# I2C16RJ45.net
KiCad netlist of a schematic drawn in EAGLE
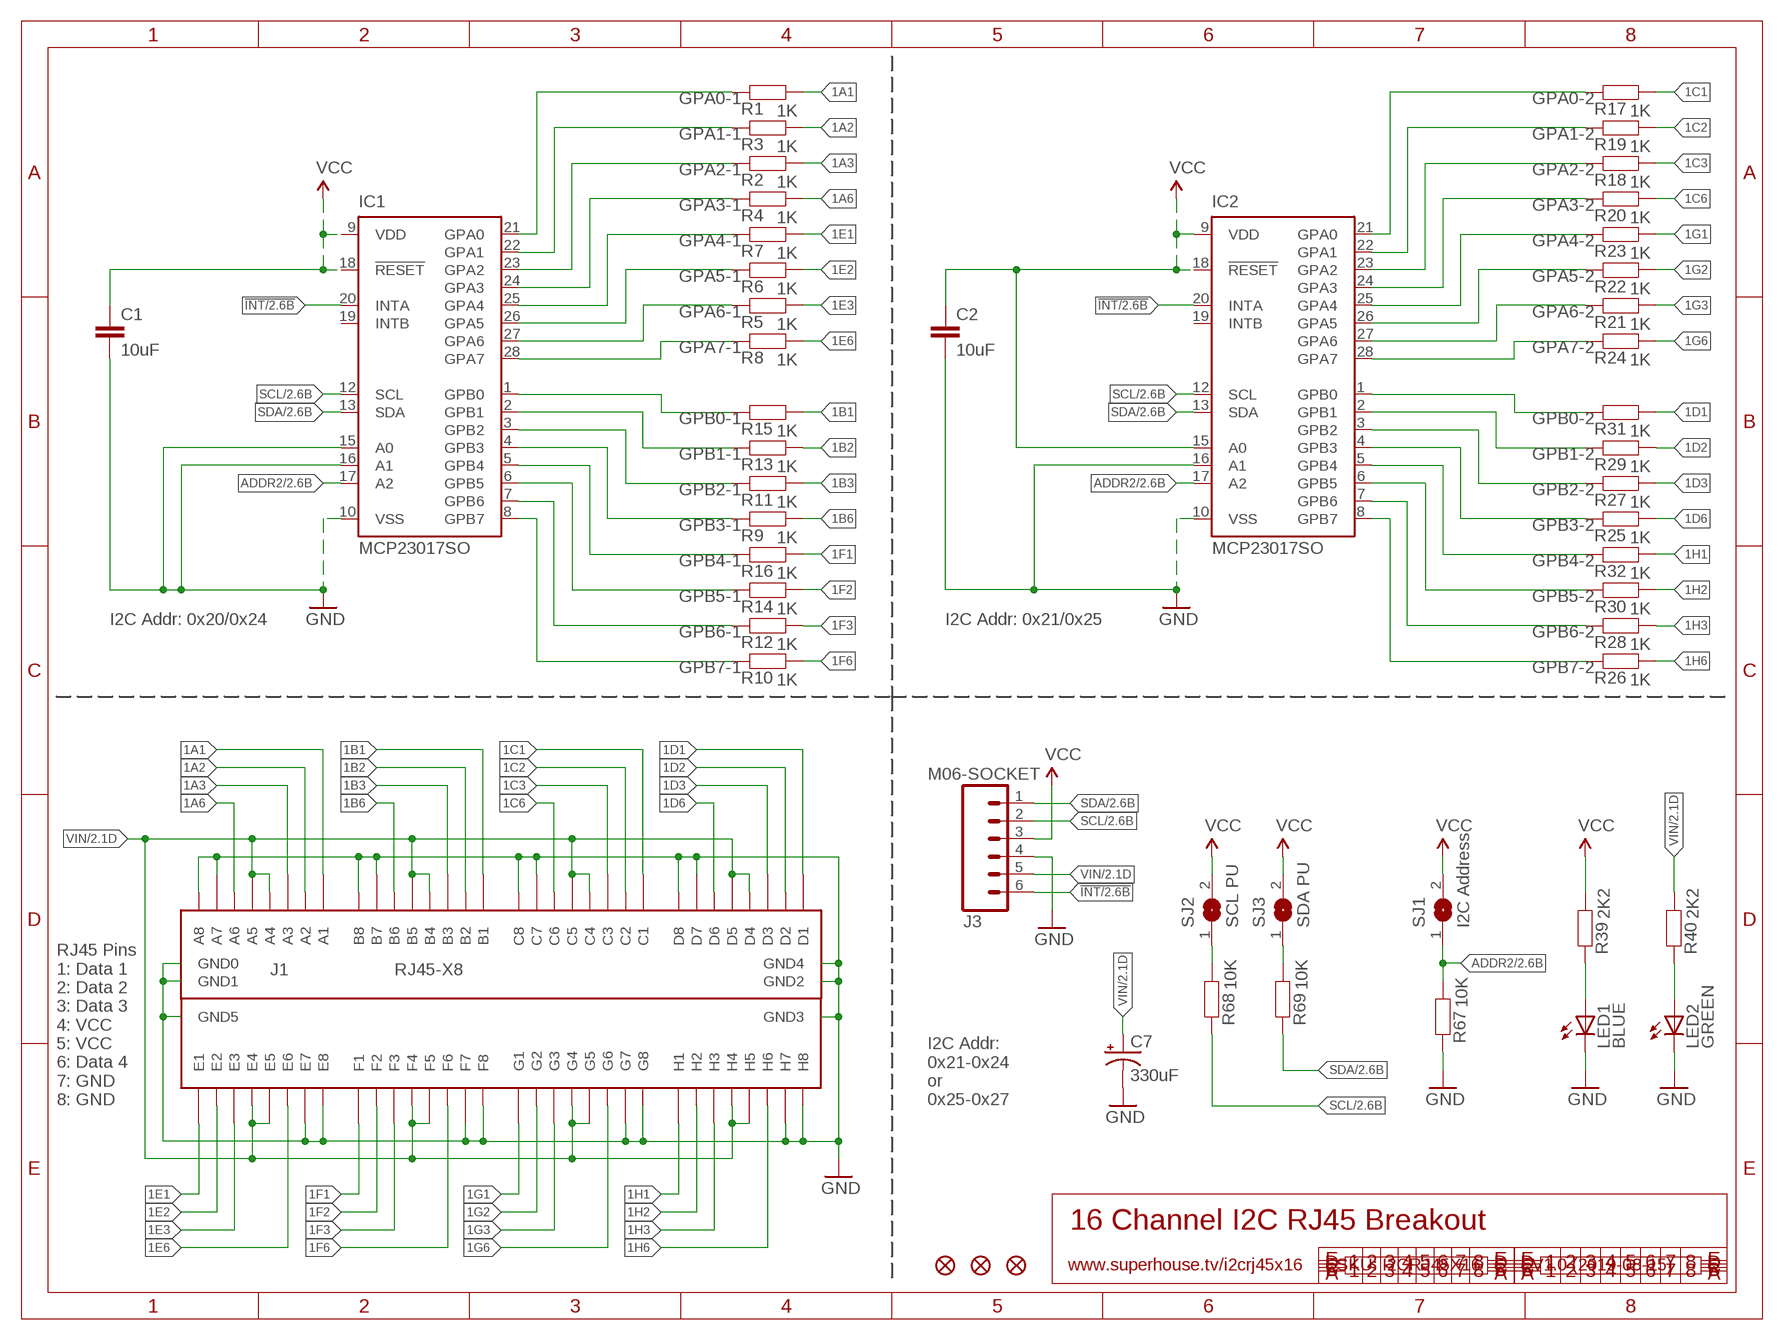
[diagram p0: schematic, sheet 1]
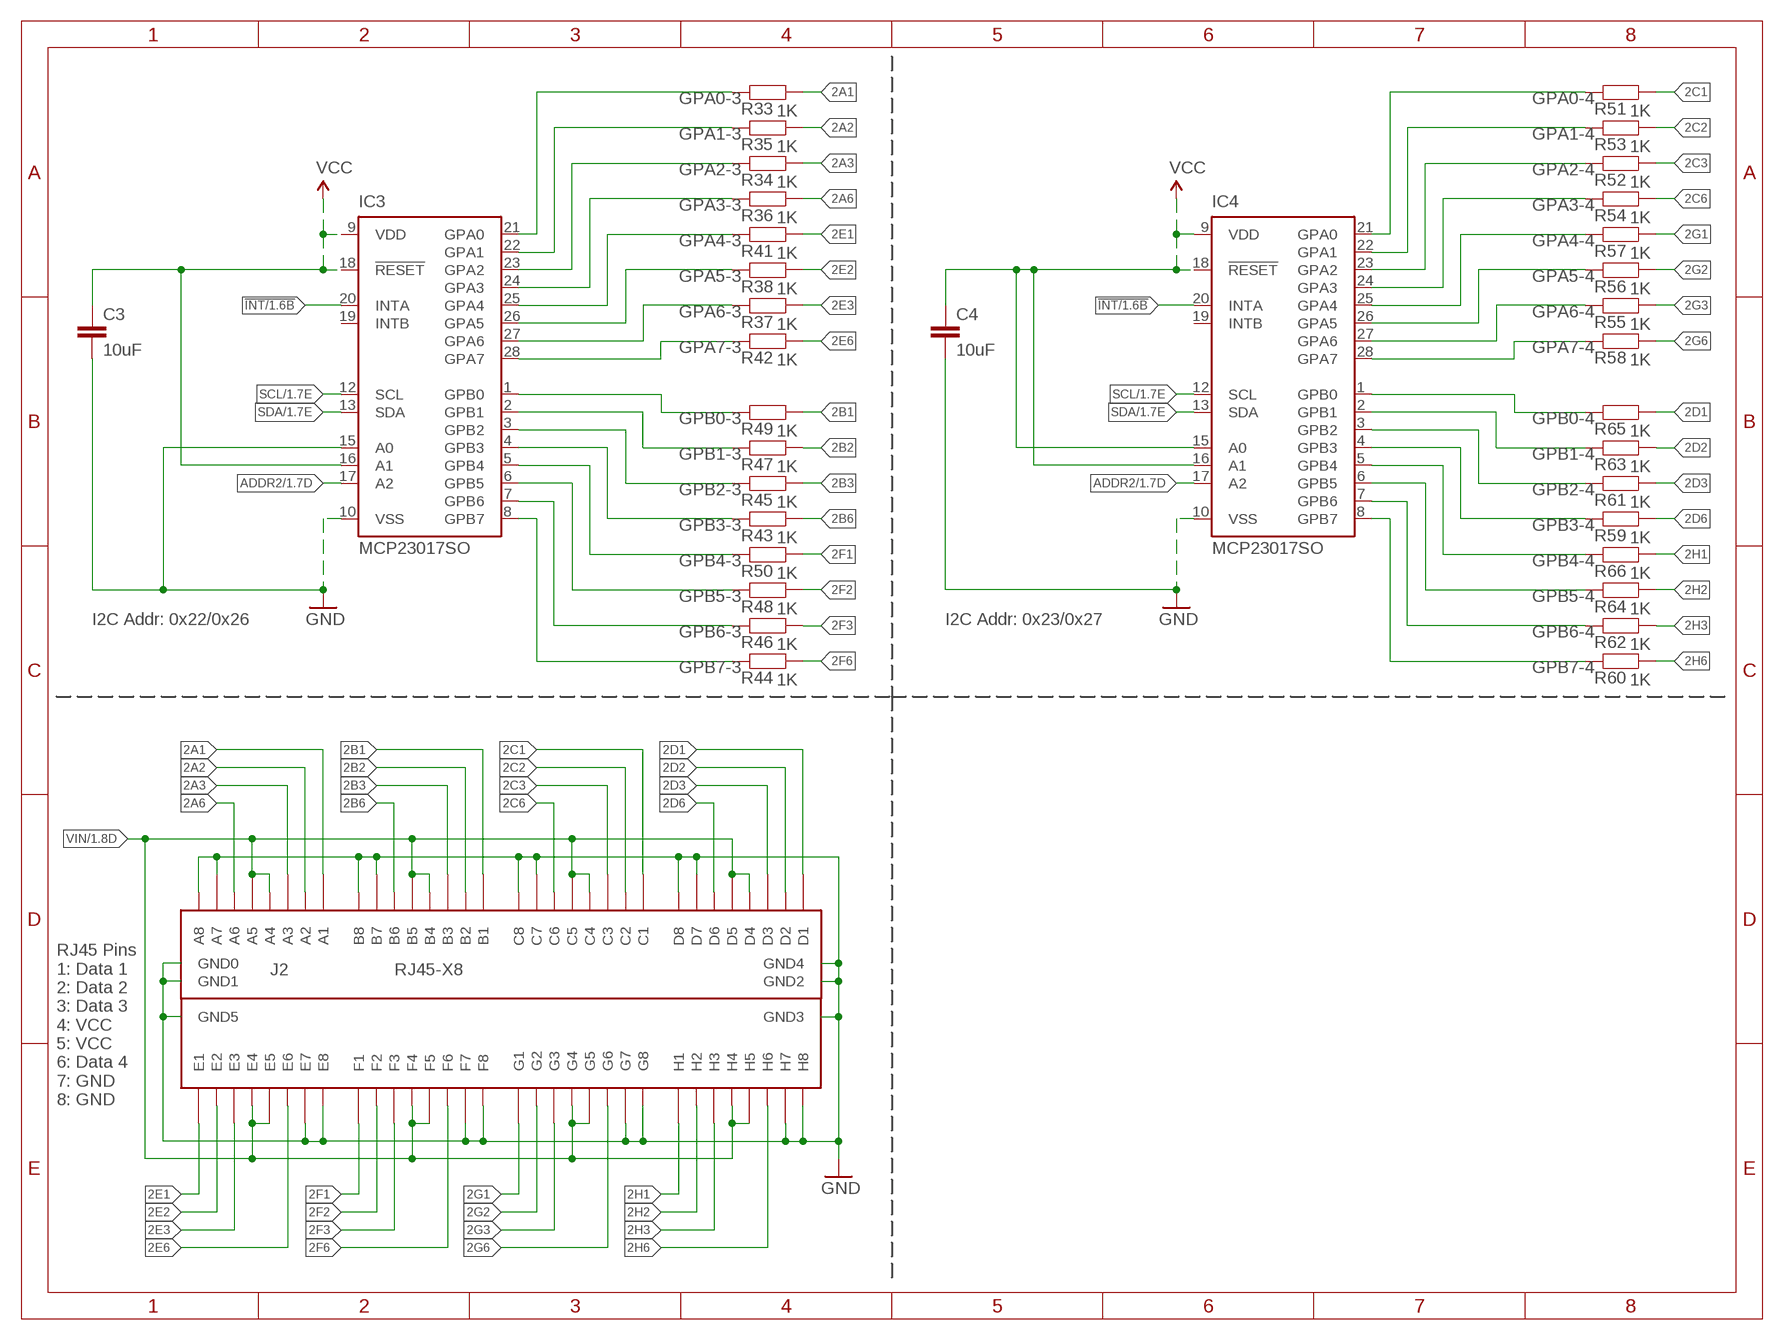
[diagram p1: schematic, sheet 2]

(export (version "E")
  (design (tool "Eeschema 10.0.6"))
  (components
    (comp (ref "C1")
      (value "10uF")
      (footprint "eagle-import:C0805")
      (libsource (lib "eagle-import") (part "CAP0805"))
    )
    (comp (ref "C2")
      (value "10uF")
      (footprint "eagle-import:C0805")
      (libsource (lib "eagle-import") (part "CAP0805"))
    )
    (comp (ref "C7")
      (value "330uF")
      (footprint "eagle-import:PANASONIC_G")
      (libsource (lib "eagle-import") (part "CAP_POLG"))
    )
    (comp (ref "FID1")
      (value "FIDUCIAL1X2.5")
      (footprint "eagle-import:FIDUCIAL-1X2.5")
      (libsource (lib "eagle-import") (part "FIDUCIAL1X2.5"))
    )
    (comp (ref "FID2")
      (value "FIDUCIAL1X2.5")
      (footprint "eagle-import:FIDUCIAL-1X2.5")
      (libsource (lib "eagle-import") (part "FIDUCIAL1X2.5"))
    )
    (comp (ref "FID3")
      (value "FIDUCIAL1X2.5")
      (footprint "eagle-import:FIDUCIAL-1X2.5")
      (libsource (lib "eagle-import") (part "FIDUCIAL1X2.5"))
    )
    (comp (ref "IC1")
      (value "MCP23017SO")
      (footprint "eagle-import:SO28W")
      (libsource (lib "eagle-import") (part "MCP23017SO"))
    )
    (comp (ref "IC2")
      (value "MCP23017SO")
      (footprint "eagle-import:SO28W")
      (libsource (lib "eagle-import") (part "MCP23017SO"))
    )
    (comp (ref "J1")
      (value "RJ45-X8")
      (footprint "eagle-import:RJ45-2X4")
      (libsource (lib "eagle-import") (part "RJ45-X8"))
    )
    (comp (ref "J3")
      (value "M06-SOCKET")
      (footprint "eagle-import:1X06-S")
      (libsource (lib "eagle-import") (part "M06-SOCKET"))
    )
    (comp (ref "LED1")
      (value "BLUE")
      (footprint "eagle-import:LED-0603")
      (libsource (lib "eagle-import") (part "LED0603"))
    )
    (comp (ref "LED2")
      (value "GREEN")
      (footprint "eagle-import:LED-0603")
      (libsource (lib "eagle-import") (part "LED0603"))
    )
    (comp (ref "R1")
      (value "1K")
      (footprint "eagle-import:R0603")
      (libsource (lib "eagle-import") (part "RESISTOR0603"))
    )
    (comp (ref "R2")
      (value "1K")
      (footprint "eagle-import:R0603")
      (libsource (lib "eagle-import") (part "RESISTOR0603"))
    )
    (comp (ref "R3")
      (value "1K")
      (footprint "eagle-import:R0603")
      (libsource (lib "eagle-import") (part "RESISTOR0603"))
    )
    (comp (ref "R4")
      (value "1K")
      (footprint "eagle-import:R0603")
      (libsource (lib "eagle-import") (part "RESISTOR0603"))
    )
    (comp (ref "R5")
      (value "1K")
      (footprint "eagle-import:R0603")
      (libsource (lib "eagle-import") (part "RESISTOR0603"))
    )
    (comp (ref "R6")
      (value "1K")
      (footprint "eagle-import:R0603")
      (libsource (lib "eagle-import") (part "RESISTOR0603"))
    )
    (comp (ref "R7")
      (value "1K")
      (footprint "eagle-import:R0603")
      (libsource (lib "eagle-import") (part "RESISTOR0603"))
    )
    (comp (ref "R8")
      (value "1K")
      (footprint "eagle-import:R0603")
      (libsource (lib "eagle-import") (part "RESISTOR0603"))
    )
    (comp (ref "R9")
      (value "1K")
      (footprint "eagle-import:R0603")
      (libsource (lib "eagle-import") (part "RESISTOR0603"))
    )
    (comp (ref "R10")
      (value "1K")
      (footprint "eagle-import:R0603")
      (libsource (lib "eagle-import") (part "RESISTOR0603"))
    )
    (comp (ref "R11")
      (value "1K")
      (footprint "eagle-import:R0603")
      (libsource (lib "eagle-import") (part "RESISTOR0603"))
    )
    (comp (ref "R12")
      (value "1K")
      (footprint "eagle-import:R0603")
      (libsource (lib "eagle-import") (part "RESISTOR0603"))
    )
    (comp (ref "R13")
      (value "1K")
      (footprint "eagle-import:R0603")
      (libsource (lib "eagle-import") (part "RESISTOR0603"))
    )
    (comp (ref "R14")
      (value "1K")
      (footprint "eagle-import:R0603")
      (libsource (lib "eagle-import") (part "RESISTOR0603"))
    )
    (comp (ref "R15")
      (value "1K")
      (footprint "eagle-import:R0603")
      (libsource (lib "eagle-import") (part "RESISTOR0603"))
    )
    (comp (ref "R16")
      (value "1K")
      (footprint "eagle-import:R0603")
      (libsource (lib "eagle-import") (part "RESISTOR0603"))
    )
    (comp (ref "R17")
      (value "1K")
      (footprint "eagle-import:R0603")
      (libsource (lib "eagle-import") (part "RESISTOR0603"))
    )
    (comp (ref "R18")
      (value "1K")
      (footprint "eagle-import:R0603")
      (libsource (lib "eagle-import") (part "RESISTOR0603"))
    )
    (comp (ref "R19")
      (value "1K")
      (footprint "eagle-import:R0603")
      (libsource (lib "eagle-import") (part "RESISTOR0603"))
    )
    (comp (ref "R20")
      (value "1K")
      (footprint "eagle-import:R0603")
      (libsource (lib "eagle-import") (part "RESISTOR0603"))
    )
    (comp (ref "R21")
      (value "1K")
      (footprint "eagle-import:R0603")
      (libsource (lib "eagle-import") (part "RESISTOR0603"))
    )
    (comp (ref "R22")
      (value "1K")
      (footprint "eagle-import:R0603")
      (libsource (lib "eagle-import") (part "RESISTOR0603"))
    )
    (comp (ref "R23")
      (value "1K")
      (footprint "eagle-import:R0603")
      (libsource (lib "eagle-import") (part "RESISTOR0603"))
    )
    (comp (ref "R24")
      (value "1K")
      (footprint "eagle-import:R0603")
      (libsource (lib "eagle-import") (part "RESISTOR0603"))
    )
    (comp (ref "R25")
      (value "1K")
      (footprint "eagle-import:R0603")
      (libsource (lib "eagle-import") (part "RESISTOR0603"))
    )
    (comp (ref "R26")
      (value "1K")
      (footprint "eagle-import:R0603")
      (libsource (lib "eagle-import") (part "RESISTOR0603"))
    )
    (comp (ref "R27")
      (value "1K")
      (footprint "eagle-import:R0603")
      (libsource (lib "eagle-import") (part "RESISTOR0603"))
    )
    (comp (ref "R28")
      (value "1K")
      (footprint "eagle-import:R0603")
      (libsource (lib "eagle-import") (part "RESISTOR0603"))
    )
    (comp (ref "R29")
      (value "1K")
      (footprint "eagle-import:R0603")
      (libsource (lib "eagle-import") (part "RESISTOR0603"))
    )
    (comp (ref "R30")
      (value "1K")
      (footprint "eagle-import:R0603")
      (libsource (lib "eagle-import") (part "RESISTOR0603"))
    )
    (comp (ref "R31")
      (value "1K")
      (footprint "eagle-import:R0603")
      (libsource (lib "eagle-import") (part "RESISTOR0603"))
    )
    (comp (ref "R32")
      (value "1K")
      (footprint "eagle-import:R0603")
      (libsource (lib "eagle-import") (part "RESISTOR0603"))
    )
    (comp (ref "R39")
      (value "2K2")
      (footprint "eagle-import:R0603")
      (libsource (lib "eagle-import") (part "RESISTOR0603"))
    )
    (comp (ref "R40")
      (value "2K2")
      (footprint "eagle-import:R0603")
      (libsource (lib "eagle-import") (part "RESISTOR0603"))
    )
    (comp (ref "R67")
      (value "10K")
      (footprint "eagle-import:R0603")
      (libsource (lib "eagle-import") (part "RESISTOR0603"))
    )
    (comp (ref "R68")
      (value "10K")
      (footprint "eagle-import:R0603")
      (libsource (lib "eagle-import") (part "RESISTOR0603"))
    )
    (comp (ref "R69")
      (value "10K")
      (footprint "eagle-import:R0603")
      (libsource (lib "eagle-import") (part "RESISTOR0603"))
    )
    (comp (ref "SJ1")
      (value "I2C Address")
      (footprint "eagle-import:SJ")
      (libsource (lib "eagle-import") (part "SJ-NORMAL"))
    )
    (comp (ref "SJ2")
      (value "SCL PU")
      (footprint "eagle-import:SJ")
      (libsource (lib "eagle-import") (part "SJ-NORMAL"))
    )
    (comp (ref "SJ3")
      (value "SDA PU")
      (footprint "eagle-import:SJ")
      (libsource (lib "eagle-import") (part "SJ-NORMAL"))
    )
    (comp (ref "C3")
      (value "10uF")
      (footprint "eagle-import:C0805")
      (libsource (lib "eagle-import") (part "CAP0805"))
    )
    (comp (ref "C4")
      (value "10uF")
      (footprint "eagle-import:C0805")
      (libsource (lib "eagle-import") (part "CAP0805"))
    )
    (comp (ref "IC3")
      (value "MCP23017SO")
      (footprint "eagle-import:SO28W")
      (libsource (lib "eagle-import") (part "MCP23017SO"))
    )
    (comp (ref "IC4")
      (value "MCP23017SO")
      (footprint "eagle-import:SO28W")
      (libsource (lib "eagle-import") (part "MCP23017SO"))
    )
    (comp (ref "J2")
      (value "RJ45-X8")
      (footprint "eagle-import:RJ45-2X4")
      (libsource (lib "eagle-import") (part "RJ45-X8"))
    )
    (comp (ref "R33")
      (value "1K")
      (footprint "eagle-import:R0603")
      (libsource (lib "eagle-import") (part "RESISTOR0603"))
    )
    (comp (ref "R34")
      (value "1K")
      (footprint "eagle-import:R0603")
      (libsource (lib "eagle-import") (part "RESISTOR0603"))
    )
    (comp (ref "R35")
      (value "1K")
      (footprint "eagle-import:R0603")
      (libsource (lib "eagle-import") (part "RESISTOR0603"))
    )
    (comp (ref "R36")
      (value "1K")
      (footprint "eagle-import:R0603")
      (libsource (lib "eagle-import") (part "RESISTOR0603"))
    )
    (comp (ref "R37")
      (value "1K")
      (footprint "eagle-import:R0603")
      (libsource (lib "eagle-import") (part "RESISTOR0603"))
    )
    (comp (ref "R38")
      (value "1K")
      (footprint "eagle-import:R0603")
      (libsource (lib "eagle-import") (part "RESISTOR0603"))
    )
    (comp (ref "R41")
      (value "1K")
      (footprint "eagle-import:R0603")
      (libsource (lib "eagle-import") (part "RESISTOR0603"))
    )
    (comp (ref "R42")
      (value "1K")
      (footprint "eagle-import:R0603")
      (libsource (lib "eagle-import") (part "RESISTOR0603"))
    )
    (comp (ref "R43")
      (value "1K")
      (footprint "eagle-import:R0603")
      (libsource (lib "eagle-import") (part "RESISTOR0603"))
    )
    (comp (ref "R44")
      (value "1K")
      (footprint "eagle-import:R0603")
      (libsource (lib "eagle-import") (part "RESISTOR0603"))
    )
    (comp (ref "R45")
      (value "1K")
      (footprint "eagle-import:R0603")
      (libsource (lib "eagle-import") (part "RESISTOR0603"))
    )
    (comp (ref "R46")
      (value "1K")
      (footprint "eagle-import:R0603")
      (libsource (lib "eagle-import") (part "RESISTOR0603"))
    )
    (comp (ref "R47")
      (value "1K")
      (footprint "eagle-import:R0603")
      (libsource (lib "eagle-import") (part "RESISTOR0603"))
    )
    (comp (ref "R48")
      (value "1K")
      (footprint "eagle-import:R0603")
      (libsource (lib "eagle-import") (part "RESISTOR0603"))
    )
    (comp (ref "R49")
      (value "1K")
      (footprint "eagle-import:R0603")
      (libsource (lib "eagle-import") (part "RESISTOR0603"))
    )
    (comp (ref "R50")
      (value "1K")
      (footprint "eagle-import:R0603")
      (libsource (lib "eagle-import") (part "RESISTOR0603"))
    )
    (comp (ref "R51")
      (value "1K")
      (footprint "eagle-import:R0603")
      (libsource (lib "eagle-import") (part "RESISTOR0603"))
    )
    (comp (ref "R52")
      (value "1K")
      (footprint "eagle-import:R0603")
      (libsource (lib "eagle-import") (part "RESISTOR0603"))
    )
    (comp (ref "R53")
      (value "1K")
      (footprint "eagle-import:R0603")
      (libsource (lib "eagle-import") (part "RESISTOR0603"))
    )
    (comp (ref "R54")
      (value "1K")
      (footprint "eagle-import:R0603")
      (libsource (lib "eagle-import") (part "RESISTOR0603"))
    )
    (comp (ref "R55")
      (value "1K")
      (footprint "eagle-import:R0603")
      (libsource (lib "eagle-import") (part "RESISTOR0603"))
    )
    (comp (ref "R56")
      (value "1K")
      (footprint "eagle-import:R0603")
      (libsource (lib "eagle-import") (part "RESISTOR0603"))
    )
    (comp (ref "R57")
      (value "1K")
      (footprint "eagle-import:R0603")
      (libsource (lib "eagle-import") (part "RESISTOR0603"))
    )
    (comp (ref "R58")
      (value "1K")
      (footprint "eagle-import:R0603")
      (libsource (lib "eagle-import") (part "RESISTOR0603"))
    )
    (comp (ref "R59")
      (value "1K")
      (footprint "eagle-import:R0603")
      (libsource (lib "eagle-import") (part "RESISTOR0603"))
    )
    (comp (ref "R60")
      (value "1K")
      (footprint "eagle-import:R0603")
      (libsource (lib "eagle-import") (part "RESISTOR0603"))
    )
    (comp (ref "R61")
      (value "1K")
      (footprint "eagle-import:R0603")
      (libsource (lib "eagle-import") (part "RESISTOR0603"))
    )
    (comp (ref "R62")
      (value "1K")
      (footprint "eagle-import:R0603")
      (libsource (lib "eagle-import") (part "RESISTOR0603"))
    )
    (comp (ref "R63")
      (value "1K")
      (footprint "eagle-import:R0603")
      (libsource (lib "eagle-import") (part "RESISTOR0603"))
    )
    (comp (ref "R64")
      (value "1K")
      (footprint "eagle-import:R0603")
      (libsource (lib "eagle-import") (part "RESISTOR0603"))
    )
    (comp (ref "R65")
      (value "1K")
      (footprint "eagle-import:R0603")
      (libsource (lib "eagle-import") (part "RESISTOR0603"))
    )
    (comp (ref "R66")
      (value "1K")
      (footprint "eagle-import:R0603")
      (libsource (lib "eagle-import") (part "RESISTOR0603"))
    )
  )
  (nets
    (net (code "1") (name "1A1") (class "Default")
      (node (ref "J1") (pin "A1") (pinfunction "A1_A1") (pintype "bidirectional"))
      (node (ref "R1") (pin "2") (pinfunction "2_2") (pintype "passive"))
    )
    (net (code "2") (name "1A2") (class "Default")
      (node (ref "J1") (pin "A2") (pinfunction "A2_A2") (pintype "bidirectional"))
      (node (ref "R3") (pin "2") (pinfunction "2_2") (pintype "passive"))
    )
    (net (code "3") (name "1A3") (class "Default")
      (node (ref "J1") (pin "A3") (pinfunction "A3_A3") (pintype "bidirectional"))
      (node (ref "R2") (pin "2") (pinfunction "2_2") (pintype "passive"))
    )
    (net (code "4") (name "1A6") (class "Default")
      (node (ref "J1") (pin "A6") (pinfunction "A6_A6") (pintype "bidirectional"))
      (node (ref "R4") (pin "2") (pinfunction "2_2") (pintype "passive"))
    )
    (net (code "5") (name "1B1") (class "Default")
      (node (ref "J1") (pin "B1") (pinfunction "B1_B1") (pintype "bidirectional"))
      (node (ref "R15") (pin "2") (pinfunction "2_2") (pintype "passive"))
    )
    (net (code "6") (name "1B2") (class "Default")
      (node (ref "J1") (pin "B2") (pinfunction "B2_B2") (pintype "bidirectional"))
      (node (ref "R13") (pin "2") (pinfunction "2_2") (pintype "passive"))
    )
    (net (code "7") (name "1B3") (class "Default")
      (node (ref "J1") (pin "B3") (pinfunction "B3_B3") (pintype "bidirectional"))
      (node (ref "R11") (pin "2") (pinfunction "2_2") (pintype "passive"))
    )
    (net (code "8") (name "1B6") (class "Default")
      (node (ref "J1") (pin "B6") (pinfunction "B6_B6") (pintype "bidirectional"))
      (node (ref "R9") (pin "2") (pinfunction "2_2") (pintype "passive"))
    )
    (net (code "9") (name "1C1") (class "Default")
      (node (ref "J1") (pin "C1") (pinfunction "C1_C1") (pintype "bidirectional"))
      (node (ref "R17") (pin "2") (pinfunction "2_2") (pintype "passive"))
    )
    (net (code "10") (name "1C2") (class "Default")
      (node (ref "J1") (pin "C2") (pinfunction "C2_C2") (pintype "bidirectional"))
      (node (ref "R19") (pin "2") (pinfunction "2_2") (pintype "passive"))
    )
    (net (code "11") (name "1C3") (class "Default")
      (node (ref "J1") (pin "C3") (pinfunction "C3_C3") (pintype "bidirectional"))
      (node (ref "R18") (pin "2") (pinfunction "2_2") (pintype "passive"))
    )
    (net (code "12") (name "1C6") (class "Default")
      (node (ref "J1") (pin "C6") (pinfunction "C6_C6") (pintype "bidirectional"))
      (node (ref "R20") (pin "2") (pinfunction "2_2") (pintype "passive"))
    )
    (net (code "13") (name "1D1") (class "Default")
      (node (ref "J1") (pin "D1") (pinfunction "D1_D1") (pintype "bidirectional"))
      (node (ref "R31") (pin "2") (pinfunction "2_2") (pintype "passive"))
    )
    (net (code "14") (name "1D2") (class "Default")
      (node (ref "J1") (pin "D2") (pinfunction "D2_D2") (pintype "bidirectional"))
      (node (ref "R29") (pin "2") (pinfunction "2_2") (pintype "passive"))
    )
    (net (code "15") (name "1D3") (class "Default")
      (node (ref "J1") (pin "D3") (pinfunction "D3_D3") (pintype "bidirectional"))
      (node (ref "R27") (pin "2") (pinfunction "2_2") (pintype "passive"))
    )
    (net (code "16") (name "1D6") (class "Default")
      (node (ref "J1") (pin "D6") (pinfunction "D6_D6") (pintype "bidirectional"))
      (node (ref "R25") (pin "2") (pinfunction "2_2") (pintype "passive"))
    )
    (net (code "17") (name "1E1") (class "Default")
      (node (ref "J1") (pin "E1") (pinfunction "E1_E1") (pintype "bidirectional"))
      (node (ref "R7") (pin "2") (pinfunction "2_2") (pintype "passive"))
    )
    (net (code "18") (name "1E2") (class "Default")
      (node (ref "J1") (pin "E2") (pinfunction "E2_E2") (pintype "bidirectional"))
      (node (ref "R6") (pin "2") (pinfunction "2_2") (pintype "passive"))
    )
    (net (code "19") (name "1E3") (class "Default")
      (node (ref "J1") (pin "E3") (pinfunction "E3_E3") (pintype "bidirectional"))
      (node (ref "R5") (pin "2") (pinfunction "2_2") (pintype "passive"))
    )
    (net (code "20") (name "1E6") (class "Default")
      (node (ref "J1") (pin "E6") (pinfunction "E6_E6") (pintype "bidirectional"))
      (node (ref "R8") (pin "2") (pinfunction "2_2") (pintype "passive"))
    )
    (net (code "21") (name "1F1") (class "Default")
      (node (ref "J1") (pin "F1") (pinfunction "F1_F1") (pintype "bidirectional"))
      (node (ref "R16") (pin "2") (pinfunction "2_2") (pintype "passive"))
    )
    (net (code "22") (name "1F2") (class "Default")
      (node (ref "J1") (pin "F2") (pinfunction "F2_F2") (pintype "bidirectional"))
      (node (ref "R14") (pin "2") (pinfunction "2_2") (pintype "passive"))
    )
    (net (code "23") (name "1F3") (class "Default")
      (node (ref "J1") (pin "F3") (pinfunction "F3_F3") (pintype "bidirectional"))
      (node (ref "R12") (pin "2") (pinfunction "2_2") (pintype "passive"))
    )
    (net (code "24") (name "1F6") (class "Default")
      (node (ref "J1") (pin "F6") (pinfunction "F6_F6") (pintype "bidirectional"))
      (node (ref "R10") (pin "2") (pinfunction "2_2") (pintype "passive"))
    )
    (net (code "25") (name "1G1") (class "Default")
      (node (ref "J1") (pin "G1") (pinfunction "G1_G1") (pintype "bidirectional"))
      (node (ref "R23") (pin "2") (pinfunction "2_2") (pintype "passive"))
    )
    (net (code "26") (name "1G2") (class "Default")
      (node (ref "J1") (pin "G2") (pinfunction "G2_G2") (pintype "bidirectional"))
      (node (ref "R22") (pin "2") (pinfunction "2_2") (pintype "passive"))
    )
    (net (code "27") (name "1G3") (class "Default")
      (node (ref "J1") (pin "G3") (pinfunction "G3_G3") (pintype "bidirectional"))
      (node (ref "R21") (pin "2") (pinfunction "2_2") (pintype "passive"))
    )
    (net (code "28") (name "1G6") (class "Default")
      (node (ref "J1") (pin "G6") (pinfunction "G6_G6") (pintype "bidirectional"))
      (node (ref "R24") (pin "2") (pinfunction "2_2") (pintype "passive"))
    )
    (net (code "29") (name "1H1") (class "Default")
      (node (ref "J1") (pin "H1") (pinfunction "H1_H1") (pintype "bidirectional"))
      (node (ref "R32") (pin "2") (pinfunction "2_2") (pintype "passive"))
    )
    (net (code "30") (name "1H2") (class "Default")
      (node (ref "J1") (pin "H2") (pinfunction "H2_H2") (pintype "bidirectional"))
      (node (ref "R30") (pin "2") (pinfunction "2_2") (pintype "passive"))
    )
    (net (code "31") (name "1H3") (class "Default")
      (node (ref "J1") (pin "H3") (pinfunction "H3_H3") (pintype "bidirectional"))
      (node (ref "R28") (pin "2") (pinfunction "2_2") (pintype "passive"))
    )
    (net (code "32") (name "1H6") (class "Default")
      (node (ref "J1") (pin "H6") (pinfunction "H6_H6") (pintype "bidirectional"))
      (node (ref "R26") (pin "2") (pinfunction "2_2") (pintype "passive"))
    )
    (net (code "33") (name "2A1") (class "Default")
      (node (ref "J2") (pin "A1") (pinfunction "A1_A1") (pintype "bidirectional"))
      (node (ref "R33") (pin "2") (pinfunction "2_2") (pintype "passive"))
    )
    (net (code "34") (name "2A2") (class "Default")
      (node (ref "J2") (pin "A2") (pinfunction "A2_A2") (pintype "bidirectional"))
      (node (ref "R35") (pin "2") (pinfunction "2_2") (pintype "passive"))
    )
    (net (code "35") (name "2A3") (class "Default")
      (node (ref "J2") (pin "A3") (pinfunction "A3_A3") (pintype "bidirectional"))
      (node (ref "R34") (pin "2") (pinfunction "2_2") (pintype "passive"))
    )
    (net (code "36") (name "2A6") (class "Default")
      (node (ref "J2") (pin "A6") (pinfunction "A6_A6") (pintype "bidirectional"))
      (node (ref "R36") (pin "2") (pinfunction "2_2") (pintype "passive"))
    )
    (net (code "37") (name "2B1") (class "Default")
      (node (ref "J2") (pin "B1") (pinfunction "B1_B1") (pintype "bidirectional"))
      (node (ref "R49") (pin "2") (pinfunction "2_2") (pintype "passive"))
    )
    (net (code "38") (name "2B2") (class "Default")
      (node (ref "J2") (pin "B2") (pinfunction "B2_B2") (pintype "bidirectional"))
      (node (ref "R47") (pin "2") (pinfunction "2_2") (pintype "passive"))
    )
    (net (code "39") (name "2B3") (class "Default")
      (node (ref "J2") (pin "B3") (pinfunction "B3_B3") (pintype "bidirectional"))
      (node (ref "R45") (pin "2") (pinfunction "2_2") (pintype "passive"))
    )
    (net (code "40") (name "2B6") (class "Default")
      (node (ref "J2") (pin "B6") (pinfunction "B6_B6") (pintype "bidirectional"))
      (node (ref "R43") (pin "2") (pinfunction "2_2") (pintype "passive"))
    )
    (net (code "41") (name "2C1") (class "Default")
      (node (ref "J2") (pin "C1") (pinfunction "C1_C1") (pintype "bidirectional"))
      (node (ref "R51") (pin "2") (pinfunction "2_2") (pintype "passive"))
    )
    (net (code "42") (name "2C2") (class "Default")
      (node (ref "J2") (pin "C2") (pinfunction "C2_C2") (pintype "bidirectional"))
      (node (ref "R53") (pin "2") (pinfunction "2_2") (pintype "passive"))
    )
    (net (code "43") (name "2C3") (class "Default")
      (node (ref "J2") (pin "C3") (pinfunction "C3_C3") (pintype "bidirectional"))
      (node (ref "R52") (pin "2") (pinfunction "2_2") (pintype "passive"))
    )
    (net (code "44") (name "2C6") (class "Default")
      (node (ref "J2") (pin "C6") (pinfunction "C6_C6") (pintype "bidirectional"))
      (node (ref "R54") (pin "2") (pinfunction "2_2") (pintype "passive"))
    )
    (net (code "45") (name "2D1") (class "Default")
      (node (ref "J2") (pin "D1") (pinfunction "D1_D1") (pintype "bidirectional"))
      (node (ref "R65") (pin "2") (pinfunction "2_2") (pintype "passive"))
    )
    (net (code "46") (name "2D2") (class "Default")
      (node (ref "J2") (pin "D2") (pinfunction "D2_D2") (pintype "bidirectional"))
      (node (ref "R63") (pin "2") (pinfunction "2_2") (pintype "passive"))
    )
    (net (code "47") (name "2D3") (class "Default")
      (node (ref "J2") (pin "D3") (pinfunction "D3_D3") (pintype "bidirectional"))
      (node (ref "R61") (pin "2") (pinfunction "2_2") (pintype "passive"))
    )
    (net (code "48") (name "2D6") (class "Default")
      (node (ref "J2") (pin "D6") (pinfunction "D6_D6") (pintype "bidirectional"))
      (node (ref "R59") (pin "2") (pinfunction "2_2") (pintype "passive"))
    )
    (net (code "49") (name "2E1") (class "Default")
      (node (ref "J2") (pin "E1") (pinfunction "E1_E1") (pintype "bidirectional"))
      (node (ref "R41") (pin "2") (pinfunction "2_2") (pintype "passive"))
    )
    (net (code "50") (name "2E2") (class "Default")
      (node (ref "J2") (pin "E2") (pinfunction "E2_E2") (pintype "bidirectional"))
      (node (ref "R38") (pin "2") (pinfunction "2_2") (pintype "passive"))
    )
    (net (code "51") (name "2E3") (class "Default")
      (node (ref "J2") (pin "E3") (pinfunction "E3_E3") (pintype "bidirectional"))
      (node (ref "R37") (pin "2") (pinfunction "2_2") (pintype "passive"))
    )
    (net (code "52") (name "2E6") (class "Default")
      (node (ref "J2") (pin "E6") (pinfunction "E6_E6") (pintype "bidirectional"))
      (node (ref "R42") (pin "2") (pinfunction "2_2") (pintype "passive"))
    )
    (net (code "53") (name "2F1") (class "Default")
      (node (ref "J2") (pin "F1") (pinfunction "F1_F1") (pintype "bidirectional"))
      (node (ref "R50") (pin "2") (pinfunction "2_2") (pintype "passive"))
    )
    (net (code "54") (name "2F2") (class "Default")
      (node (ref "J2") (pin "F2") (pinfunction "F2_F2") (pintype "bidirectional"))
      (node (ref "R48") (pin "2") (pinfunction "2_2") (pintype "passive"))
    )
    (net (code "55") (name "2F3") (class "Default")
      (node (ref "J2") (pin "F3") (pinfunction "F3_F3") (pintype "bidirectional"))
      (node (ref "R46") (pin "2") (pinfunction "2_2") (pintype "passive"))
    )
    (net (code "56") (name "2F6") (class "Default")
      (node (ref "J2") (pin "F6") (pinfunction "F6_F6") (pintype "bidirectional"))
      (node (ref "R44") (pin "2") (pinfunction "2_2") (pintype "passive"))
    )
    (net (code "57") (name "2G1") (class "Default")
      (node (ref "J2") (pin "G1") (pinfunction "G1_G1") (pintype "bidirectional"))
      (node (ref "R57") (pin "2") (pinfunction "2_2") (pintype "passive"))
    )
    (net (code "58") (name "2G2") (class "Default")
      (node (ref "J2") (pin "G2") (pinfunction "G2_G2") (pintype "bidirectional"))
      (node (ref "R56") (pin "2") (pinfunction "2_2") (pintype "passive"))
    )
    (net (code "59") (name "2G3") (class "Default")
      (node (ref "J2") (pin "G3") (pinfunction "G3_G3") (pintype "bidirectional"))
      (node (ref "R55") (pin "2") (pinfunction "2_2") (pintype "passive"))
    )
    (net (code "60") (name "2G6") (class "Default")
      (node (ref "J2") (pin "G6") (pinfunction "G6_G6") (pintype "bidirectional"))
      (node (ref "R58") (pin "2") (pinfunction "2_2") (pintype "passive"))
    )
    (net (code "61") (name "2H1") (class "Default")
      (node (ref "J2") (pin "H1") (pinfunction "H1_H1") (pintype "bidirectional"))
      (node (ref "R66") (pin "2") (pinfunction "2_2") (pintype "passive"))
    )
    (net (code "62") (name "2H2") (class "Default")
      (node (ref "J2") (pin "H2") (pinfunction "H2_H2") (pintype "bidirectional"))
      (node (ref "R64") (pin "2") (pinfunction "2_2") (pintype "passive"))
    )
    (net (code "63") (name "2H3") (class "Default")
      (node (ref "J2") (pin "H3") (pinfunction "H3_H3") (pintype "bidirectional"))
      (node (ref "R62") (pin "2") (pinfunction "2_2") (pintype "passive"))
    )
    (net (code "64") (name "2H6") (class "Default")
      (node (ref "J2") (pin "H6") (pinfunction "H6_H6") (pintype "bidirectional"))
      (node (ref "R60") (pin "2") (pinfunction "2_2") (pintype "passive"))
    )
    (net (code "65") (name "ADDR2") (class "Default")
      (node (ref "IC1") (pin "17") (pinfunction "A2_17") (pintype "input"))
      (node (ref "IC2") (pin "17") (pinfunction "A2_17") (pintype "input"))
      (node (ref "IC3") (pin "17") (pinfunction "A2_17") (pintype "input"))
      (node (ref "IC4") (pin "17") (pinfunction "A2_17") (pintype "input"))
      (node (ref "R67") (pin "2") (pinfunction "2_2") (pintype "passive"))
      (node (ref "SJ1") (pin "1") (pinfunction "1_1") (pintype "passive"))
    )
    (net (code "66") (name "GND") (class "Default")
      (node (ref "C1") (pin "2") (pinfunction "2_2") (pintype "passive"))
      (node (ref "C2") (pin "2") (pinfunction "2_2") (pintype "passive"))
      (node (ref "C3") (pin "2") (pinfunction "2_2") (pintype "passive"))
      (node (ref "C4") (pin "2") (pinfunction "2_2") (pintype "passive"))
      (node (ref "C7") (pin "-") (pinfunction "-_-") (pintype "passive"))
      (node (ref "IC1") (pin "10") (pinfunction "VSS_10") (pintype "power_in"))
      (node (ref "IC1") (pin "15") (pinfunction "A0_15") (pintype "input"))
      (node (ref "IC1") (pin "16") (pinfunction "A1_16") (pintype "input"))
      (node (ref "IC2") (pin "10") (pinfunction "VSS_10") (pintype "power_in"))
      (node (ref "IC2") (pin "16") (pinfunction "A1_16") (pintype "input"))
      (node (ref "IC3") (pin "10") (pinfunction "VSS_10") (pintype "power_in"))
      (node (ref "IC3") (pin "15") (pinfunction "A0_15") (pintype "input"))
      (node (ref "IC4") (pin "10") (pinfunction "VSS_10") (pintype "power_in"))
      (node (ref "J1") (pin "A7") (pinfunction "A7_A7") (pintype "bidirectional"))
      (node (ref "J1") (pin "A8") (pinfunction "A8_A8") (pintype "bidirectional"))
      (node (ref "J1") (pin "B7") (pinfunction "B7_B7") (pintype "bidirectional"))
      (node (ref "J1") (pin "B8") (pinfunction "B8_B8") (pintype "bidirectional"))
      (node (ref "J1") (pin "C7") (pinfunction "C7_C7") (pintype "bidirectional"))
      (node (ref "J1") (pin "C8") (pinfunction "C8_C8") (pintype "bidirectional"))
      (node (ref "J1") (pin "D7") (pinfunction "D7_D7") (pintype "bidirectional"))
      (node (ref "J1") (pin "D8") (pinfunction "D8_D8") (pintype "bidirectional"))
      (node (ref "J1") (pin "E7") (pinfunction "E7_E7") (pintype "bidirectional"))
      (node (ref "J1") (pin "E8") (pinfunction "E8_E8") (pintype "bidirectional"))
      (node (ref "J1") (pin "F7") (pinfunction "F7_F7") (pintype "bidirectional"))
      (node (ref "J1") (pin "F8") (pinfunction "F8_F8") (pintype "bidirectional"))
      (node (ref "J1") (pin "G7") (pinfunction "G7_G7") (pintype "bidirectional"))
      (node (ref "J1") (pin "G8") (pinfunction "G8_G8") (pintype "bidirectional"))
      (node (ref "J1") (pin "GND0") (pinfunction "GND0_GND0") (pintype "power_in"))
      (node (ref "J1") (pin "GND1") (pinfunction "GND1_GND1") (pintype "power_in"))
      (node (ref "J1") (pin "GND2") (pinfunction "GND2_GND2") (pintype "power_in"))
      (node (ref "J1") (pin "GND3") (pinfunction "GND3_GND3") (pintype "power_in"))
      (node (ref "J1") (pin "GND4") (pinfunction "GND4_GND4") (pintype "power_in"))
      (node (ref "J1") (pin "GND5") (pinfunction "GND5_GND5") (pintype "power_in"))
      (node (ref "J1") (pin "H7") (pinfunction "H7_H7") (pintype "bidirectional"))
      (node (ref "J1") (pin "H8") (pinfunction "H8_H8") (pintype "bidirectional"))
      (node (ref "J2") (pin "A7") (pinfunction "A7_A7") (pintype "bidirectional"))
      (node (ref "J2") (pin "A8") (pinfunction "A8_A8") (pintype "bidirectional"))
      (node (ref "J2") (pin "B7") (pinfunction "B7_B7") (pintype "bidirectional"))
      (node (ref "J2") (pin "B8") (pinfunction "B8_B8") (pintype "bidirectional"))
      (node (ref "J2") (pin "C7") (pinfunction "C7_C7") (pintype "bidirectional"))
      (node (ref "J2") (pin "C8") (pinfunction "C8_C8") (pintype "bidirectional"))
      (node (ref "J2") (pin "D7") (pinfunction "D7_D7") (pintype "bidirectional"))
      (node (ref "J2") (pin "D8") (pinfunction "D8_D8") (pintype "bidirectional"))
      (node (ref "J2") (pin "E7") (pinfunction "E7_E7") (pintype "bidirectional"))
      (node (ref "J2") (pin "E8") (pinfunction "E8_E8") (pintype "bidirectional"))
      (node (ref "J2") (pin "F7") (pinfunction "F7_F7") (pintype "bidirectional"))
      (node (ref "J2") (pin "F8") (pinfunction "F8_F8") (pintype "bidirectional"))
      (node (ref "J2") (pin "G7") (pinfunction "G7_G7") (pintype "bidirectional"))
      (node (ref "J2") (pin "G8") (pinfunction "G8_G8") (pintype "bidirectional"))
      (node (ref "J2") (pin "GND0") (pinfunction "GND0_GND0") (pintype "power_in"))
      (node (ref "J2") (pin "GND1") (pinfunction "GND1_GND1") (pintype "power_in"))
      (node (ref "J2") (pin "GND2") (pinfunction "GND2_GND2") (pintype "power_in"))
      (node (ref "J2") (pin "GND3") (pinfunction "GND3_GND3") (pintype "power_in"))
      (node (ref "J2") (pin "GND4") (pinfunction "GND4_GND4") (pintype "power_in"))
      (node (ref "J2") (pin "GND5") (pinfunction "GND5_GND5") (pintype "power_in"))
      (node (ref "J2") (pin "H7") (pinfunction "H7_H7") (pintype "bidirectional"))
      (node (ref "J2") (pin "H8") (pinfunction "H8_H8") (pintype "bidirectional"))
      (node (ref "J3") (pin "4") (pinfunction "4_4") (pintype "passive"))
      (node (ref "LED1") (pin "C") (pinfunction "C_C") (pintype "passive"))
      (node (ref "LED2") (pin "C") (pinfunction "C_C") (pintype "passive"))
      (node (ref "R67") (pin "1") (pinfunction "1_1") (pintype "passive"))
    )
    (net (code "67") (name "GPA0-1") (class "Default")
      (node (ref "IC1") (pin "21") (pinfunction "GPA0_21") (pintype "bidirectional"))
      (node (ref "R1") (pin "1") (pinfunction "1_1") (pintype "passive"))
    )
    (net (code "68") (name "GPA0-2") (class "Default")
      (node (ref "IC2") (pin "21") (pinfunction "GPA0_21") (pintype "bidirectional"))
      (node (ref "R17") (pin "1") (pinfunction "1_1") (pintype "passive"))
    )
    (net (code "69") (name "GPA0-3") (class "Default")
      (node (ref "IC3") (pin "21") (pinfunction "GPA0_21") (pintype "bidirectional"))
      (node (ref "R33") (pin "1") (pinfunction "1_1") (pintype "passive"))
    )
    (net (code "70") (name "GPA0-4") (class "Default")
      (node (ref "IC4") (pin "21") (pinfunction "GPA0_21") (pintype "bidirectional"))
      (node (ref "R51") (pin "1") (pinfunction "1_1") (pintype "passive"))
    )
    (net (code "71") (name "GPA1-1") (class "Default")
      (node (ref "IC1") (pin "22") (pinfunction "GPA1_22") (pintype "bidirectional"))
      (node (ref "R3") (pin "1") (pinfunction "1_1") (pintype "passive"))
    )
    (net (code "72") (name "GPA1-2") (class "Default")
      (node (ref "IC2") (pin "22") (pinfunction "GPA1_22") (pintype "bidirectional"))
      (node (ref "R19") (pin "1") (pinfunction "1_1") (pintype "passive"))
    )
    (net (code "73") (name "GPA1-3") (class "Default")
      (node (ref "IC3") (pin "22") (pinfunction "GPA1_22") (pintype "bidirectional"))
      (node (ref "R35") (pin "1") (pinfunction "1_1") (pintype "passive"))
    )
    (net (code "74") (name "GPA1-4") (class "Default")
      (node (ref "IC4") (pin "22") (pinfunction "GPA1_22") (pintype "bidirectional"))
      (node (ref "R53") (pin "1") (pinfunction "1_1") (pintype "passive"))
    )
    (net (code "75") (name "GPA2-1") (class "Default")
      (node (ref "IC1") (pin "23") (pinfunction "GPA2_23") (pintype "bidirectional"))
      (node (ref "R2") (pin "1") (pinfunction "1_1") (pintype "passive"))
    )
    (net (code "76") (name "GPA2-2") (class "Default")
      (node (ref "IC2") (pin "23") (pinfunction "GPA2_23") (pintype "bidirectional"))
      (node (ref "R18") (pin "1") (pinfunction "1_1") (pintype "passive"))
    )
    (net (code "77") (name "GPA2-3") (class "Default")
      (node (ref "IC3") (pin "23") (pinfunction "GPA2_23") (pintype "bidirectional"))
      (node (ref "R34") (pin "1") (pinfunction "1_1") (pintype "passive"))
    )
    (net (code "78") (name "GPA2-4") (class "Default")
      (node (ref "IC4") (pin "23") (pinfunction "GPA2_23") (pintype "bidirectional"))
      (node (ref "R52") (pin "1") (pinfunction "1_1") (pintype "passive"))
    )
    (net (code "79") (name "GPA3-1") (class "Default")
      (node (ref "IC1") (pin "24") (pinfunction "GPA3_24") (pintype "bidirectional"))
      (node (ref "R4") (pin "1") (pinfunction "1_1") (pintype "passive"))
    )
    (net (code "80") (name "GPA3-2") (class "Default")
      (node (ref "IC2") (pin "24") (pinfunction "GPA3_24") (pintype "bidirectional"))
      (node (ref "R20") (pin "1") (pinfunction "1_1") (pintype "passive"))
    )
    (net (code "81") (name "GPA3-3") (class "Default")
      (node (ref "IC3") (pin "24") (pinfunction "GPA3_24") (pintype "bidirectional"))
      (node (ref "R36") (pin "1") (pinfunction "1_1") (pintype "passive"))
    )
    (net (code "82") (name "GPA3-4") (class "Default")
      (node (ref "IC4") (pin "24") (pinfunction "GPA3_24") (pintype "bidirectional"))
      (node (ref "R54") (pin "1") (pinfunction "1_1") (pintype "passive"))
    )
    (net (code "83") (name "GPA4-1") (class "Default")
      (node (ref "IC1") (pin "25") (pinfunction "GPA4_25") (pintype "bidirectional"))
      (node (ref "R7") (pin "1") (pinfunction "1_1") (pintype "passive"))
    )
    (net (code "84") (name "GPA4-2") (class "Default")
      (node (ref "IC2") (pin "25") (pinfunction "GPA4_25") (pintype "bidirectional"))
      (node (ref "R23") (pin "1") (pinfunction "1_1") (pintype "passive"))
    )
    (net (code "85") (name "GPA4-3") (class "Default")
      (node (ref "IC3") (pin "25") (pinfunction "GPA4_25") (pintype "bidirectional"))
      (node (ref "R41") (pin "1") (pinfunction "1_1") (pintype "passive"))
    )
    (net (code "86") (name "GPA4-4") (class "Default")
      (node (ref "IC4") (pin "25") (pinfunction "GPA4_25") (pintype "bidirectional"))
      (node (ref "R57") (pin "1") (pinfunction "1_1") (pintype "passive"))
    )
    (net (code "87") (name "GPA5-1") (class "Default")
      (node (ref "IC1") (pin "26") (pinfunction "GPA5_26") (pintype "bidirectional"))
      (node (ref "R6") (pin "1") (pinfunction "1_1") (pintype "passive"))
    )
    (net (code "88") (name "GPA5-2") (class "Default")
      (node (ref "IC2") (pin "26") (pinfunction "GPA5_26") (pintype "bidirectional"))
      (node (ref "R22") (pin "1") (pinfunction "1_1") (pintype "passive"))
    )
    (net (code "89") (name "GPA5-3") (class "Default")
      (node (ref "IC3") (pin "26") (pinfunction "GPA5_26") (pintype "bidirectional"))
      (node (ref "R38") (pin "1") (pinfunction "1_1") (pintype "passive"))
    )
    (net (code "90") (name "GPA5-4") (class "Default")
      (node (ref "IC4") (pin "26") (pinfunction "GPA5_26") (pintype "bidirectional"))
      (node (ref "R56") (pin "1") (pinfunction "1_1") (pintype "passive"))
    )
    (net (code "91") (name "GPA6-1") (class "Default")
      (node (ref "IC1") (pin "27") (pinfunction "GPA6_27") (pintype "bidirectional"))
      (node (ref "R5") (pin "1") (pinfunction "1_1") (pintype "passive"))
    )
    (net (code "92") (name "GPA6-2") (class "Default")
      (node (ref "IC2") (pin "27") (pinfunction "GPA6_27") (pintype "bidirectional"))
      (node (ref "R21") (pin "1") (pinfunction "1_1") (pintype "passive"))
    )
    (net (code "93") (name "GPA6-3") (class "Default")
      (node (ref "IC3") (pin "27") (pinfunction "GPA6_27") (pintype "bidirectional"))
      (node (ref "R37") (pin "1") (pinfunction "1_1") (pintype "passive"))
    )
    (net (code "94") (name "GPA6-4") (class "Default")
      (node (ref "IC4") (pin "27") (pinfunction "GPA6_27") (pintype "bidirectional"))
      (node (ref "R55") (pin "1") (pinfunction "1_1") (pintype "passive"))
    )
    (net (code "95") (name "GPA7-1") (class "Default")
      (node (ref "IC1") (pin "28") (pinfunction "GPA7_28") (pintype "bidirectional"))
      (node (ref "R8") (pin "1") (pinfunction "1_1") (pintype "passive"))
    )
    (net (code "96") (name "GPA7-2") (class "Default")
      (node (ref "IC2") (pin "28") (pinfunction "GPA7_28") (pintype "bidirectional"))
      (node (ref "R24") (pin "1") (pinfunction "1_1") (pintype "passive"))
    )
    (net (code "97") (name "GPA7-3") (class "Default")
      (node (ref "IC3") (pin "28") (pinfunction "GPA7_28") (pintype "bidirectional"))
      (node (ref "R42") (pin "1") (pinfunction "1_1") (pintype "passive"))
    )
    (net (code "98") (name "GPA7-4") (class "Default")
      (node (ref "IC4") (pin "28") (pinfunction "GPA7_28") (pintype "bidirectional"))
      (node (ref "R58") (pin "1") (pinfunction "1_1") (pintype "passive"))
    )
    (net (code "99") (name "GPB0-1") (class "Default")
      (node (ref "IC1") (pin "1") (pinfunction "GPB0_1") (pintype "bidirectional"))
      (node (ref "R15") (pin "1") (pinfunction "1_1") (pintype "passive"))
    )
    (net (code "100") (name "GPB0-2") (class "Default")
      (node (ref "IC2") (pin "1") (pinfunction "GPB0_1") (pintype "bidirectional"))
      (node (ref "R31") (pin "1") (pinfunction "1_1") (pintype "passive"))
    )
    (net (code "101") (name "GPB0-3") (class "Default")
      (node (ref "IC3") (pin "1") (pinfunction "GPB0_1") (pintype "bidirectional"))
      (node (ref "R49") (pin "1") (pinfunction "1_1") (pintype "passive"))
    )
    (net (code "102") (name "GPB0-4") (class "Default")
      (node (ref "IC4") (pin "1") (pinfunction "GPB0_1") (pintype "bidirectional"))
      (node (ref "R65") (pin "1") (pinfunction "1_1") (pintype "passive"))
    )
    (net (code "103") (name "GPB1-1") (class "Default")
      (node (ref "IC1") (pin "2") (pinfunction "GPB1_2") (pintype "bidirectional"))
      (node (ref "R13") (pin "1") (pinfunction "1_1") (pintype "passive"))
    )
    (net (code "104") (name "GPB1-2") (class "Default")
      (node (ref "IC2") (pin "2") (pinfunction "GPB1_2") (pintype "bidirectional"))
      (node (ref "R29") (pin "1") (pinfunction "1_1") (pintype "passive"))
    )
    (net (code "105") (name "GPB1-3") (class "Default")
      (node (ref "IC3") (pin "2") (pinfunction "GPB1_2") (pintype "bidirectional"))
      (node (ref "R47") (pin "1") (pinfunction "1_1") (pintype "passive"))
    )
    (net (code "106") (name "GPB1-4") (class "Default")
      (node (ref "IC4") (pin "2") (pinfunction "GPB1_2") (pintype "bidirectional"))
      (node (ref "R63") (pin "1") (pinfunction "1_1") (pintype "passive"))
    )
    (net (code "107") (name "GPB2-1") (class "Default")
      (node (ref "IC1") (pin "3") (pinfunction "GPB2_3") (pintype "bidirectional"))
      (node (ref "R11") (pin "1") (pinfunction "1_1") (pintype "passive"))
    )
    (net (code "108") (name "GPB2-2") (class "Default")
      (node (ref "IC2") (pin "3") (pinfunction "GPB2_3") (pintype "bidirectional"))
      (node (ref "R27") (pin "1") (pinfunction "1_1") (pintype "passive"))
    )
    (net (code "109") (name "GPB2-3") (class "Default")
      (node (ref "IC3") (pin "3") (pinfunction "GPB2_3") (pintype "bidirectional"))
      (node (ref "R45") (pin "1") (pinfunction "1_1") (pintype "passive"))
    )
    (net (code "110") (name "GPB2-4") (class "Default")
      (node (ref "IC4") (pin "3") (pinfunction "GPB2_3") (pintype "bidirectional"))
      (node (ref "R61") (pin "1") (pinfunction "1_1") (pintype "passive"))
    )
    (net (code "111") (name "GPB3-1") (class "Default")
      (node (ref "IC1") (pin "4") (pinfunction "GPB3_4") (pintype "bidirectional"))
      (node (ref "R9") (pin "1") (pinfunction "1_1") (pintype "passive"))
    )
    (net (code "112") (name "GPB3-2") (class "Default")
      (node (ref "IC2") (pin "4") (pinfunction "GPB3_4") (pintype "bidirectional"))
      (node (ref "R25") (pin "1") (pinfunction "1_1") (pintype "passive"))
    )
    (net (code "113") (name "GPB3-3") (class "Default")
      (node (ref "IC3") (pin "4") (pinfunction "GPB3_4") (pintype "bidirectional"))
      (node (ref "R43") (pin "1") (pinfunction "1_1") (pintype "passive"))
    )
    (net (code "114") (name "GPB3-4") (class "Default")
      (node (ref "IC4") (pin "4") (pinfunction "GPB3_4") (pintype "bidirectional"))
      (node (ref "R59") (pin "1") (pinfunction "1_1") (pintype "passive"))
    )
    (net (code "115") (name "GPB4-1") (class "Default")
      (node (ref "IC1") (pin "5") (pinfunction "GPB4_5") (pintype "bidirectional"))
      (node (ref "R16") (pin "1") (pinfunction "1_1") (pintype "passive"))
    )
    (net (code "116") (name "GPB4-2") (class "Default")
      (node (ref "IC2") (pin "5") (pinfunction "GPB4_5") (pintype "bidirectional"))
      (node (ref "R32") (pin "1") (pinfunction "1_1") (pintype "passive"))
    )
    (net (code "117") (name "GPB4-3") (class "Default")
      (node (ref "IC3") (pin "5") (pinfunction "GPB4_5") (pintype "bidirectional"))
      (node (ref "R50") (pin "1") (pinfunction "1_1") (pintype "passive"))
    )
    (net (code "118") (name "GPB4-4") (class "Default")
      (node (ref "IC4") (pin "5") (pinfunction "GPB4_5") (pintype "bidirectional"))
      (node (ref "R66") (pin "1") (pinfunction "1_1") (pintype "passive"))
    )
    (net (code "119") (name "GPB5-1") (class "Default")
      (node (ref "IC1") (pin "6") (pinfunction "GPB5_6") (pintype "bidirectional"))
      (node (ref "R14") (pin "1") (pinfunction "1_1") (pintype "passive"))
    )
    (net (code "120") (name "GPB5-2") (class "Default")
      (node (ref "IC2") (pin "6") (pinfunction "GPB5_6") (pintype "bidirectional"))
      (node (ref "R30") (pin "1") (pinfunction "1_1") (pintype "passive"))
    )
    (net (code "121") (name "GPB5-3") (class "Default")
      (node (ref "IC3") (pin "6") (pinfunction "GPB5_6") (pintype "bidirectional"))
      (node (ref "R48") (pin "1") (pinfunction "1_1") (pintype "passive"))
    )
    (net (code "122") (name "GPB5-4") (class "Default")
      (node (ref "IC4") (pin "6") (pinfunction "GPB5_6") (pintype "bidirectional"))
      (node (ref "R64") (pin "1") (pinfunction "1_1") (pintype "passive"))
    )
    (net (code "123") (name "GPB6-1") (class "Default")
      (node (ref "IC1") (pin "7") (pinfunction "GPB6_7") (pintype "bidirectional"))
      (node (ref "R12") (pin "1") (pinfunction "1_1") (pintype "passive"))
    )
    (net (code "124") (name "GPB6-2") (class "Default")
      (node (ref "IC2") (pin "7") (pinfunction "GPB6_7") (pintype "bidirectional"))
      (node (ref "R28") (pin "1") (pinfunction "1_1") (pintype "passive"))
    )
    (net (code "125") (name "GPB6-3") (class "Default")
      (node (ref "IC3") (pin "7") (pinfunction "GPB6_7") (pintype "bidirectional"))
      (node (ref "R46") (pin "1") (pinfunction "1_1") (pintype "passive"))
    )
    (net (code "126") (name "GPB6-4") (class "Default")
      (node (ref "IC4") (pin "7") (pinfunction "GPB6_7") (pintype "bidirectional"))
      (node (ref "R62") (pin "1") (pinfunction "1_1") (pintype "passive"))
    )
    (net (code "127") (name "GPB7-1") (class "Default")
      (node (ref "IC1") (pin "8") (pinfunction "GPB7_8") (pintype "bidirectional"))
      (node (ref "R10") (pin "1") (pinfunction "1_1") (pintype "passive"))
    )
    (net (code "128") (name "GPB7-2") (class "Default")
      (node (ref "IC2") (pin "8") (pinfunction "GPB7_8") (pintype "bidirectional"))
      (node (ref "R26") (pin "1") (pinfunction "1_1") (pintype "passive"))
    )
    (net (code "129") (name "GPB7-3") (class "Default")
      (node (ref "IC3") (pin "8") (pinfunction "GPB7_8") (pintype "bidirectional"))
      (node (ref "R44") (pin "1") (pinfunction "1_1") (pintype "passive"))
    )
    (net (code "130") (name "GPB7-4") (class "Default")
      (node (ref "IC4") (pin "8") (pinfunction "GPB7_8") (pintype "bidirectional"))
      (node (ref "R60") (pin "1") (pinfunction "1_1") (pintype "passive"))
    )
    (net (code "131") (name "Net-(LED1-PadA)") (class "Default")
      (node (ref "LED1") (pin "A") (pinfunction "A_A") (pintype "passive"))
      (node (ref "R39") (pin "1") (pinfunction "1_1") (pintype "passive"))
    )
    (net (code "132") (name "Net-(LED2-PadA)") (class "Default")
      (node (ref "LED2") (pin "A") (pinfunction "A_A") (pintype "passive"))
      (node (ref "R40") (pin "1") (pinfunction "1_1") (pintype "passive"))
    )
    (net (code "133") (name "Net-(R68-Pad2)") (class "Default")
      (node (ref "R68") (pin "2") (pinfunction "2_2") (pintype "passive"))
      (node (ref "SJ2") (pin "1") (pinfunction "1_1") (pintype "passive"))
    )
    (net (code "134") (name "Net-(R69-Pad2)") (class "Default")
      (node (ref "R69") (pin "2") (pinfunction "2_2") (pintype "passive"))
      (node (ref "SJ3") (pin "1") (pinfunction "1_1") (pintype "passive"))
    )
    (net (code "135") (name "SCL") (class "Default")
      (node (ref "IC1") (pin "12") (pinfunction "SCL_12") (pintype "input"))
      (node (ref "IC2") (pin "12") (pinfunction "SCL_12") (pintype "input"))
      (node (ref "IC3") (pin "12") (pinfunction "SCL_12") (pintype "input"))
      (node (ref "IC4") (pin "12") (pinfunction "SCL_12") (pintype "input"))
      (node (ref "J3") (pin "2") (pinfunction "2_2") (pintype "passive"))
      (node (ref "R68") (pin "1") (pinfunction "1_1") (pintype "passive"))
    )
    (net (code "136") (name "SDA") (class "Default")
      (node (ref "IC1") (pin "13") (pinfunction "SDA_13") (pintype "bidirectional"))
      (node (ref "IC2") (pin "13") (pinfunction "SDA_13") (pintype "bidirectional"))
      (node (ref "IC3") (pin "13") (pinfunction "SDA_13") (pintype "bidirectional"))
      (node (ref "IC4") (pin "13") (pinfunction "SDA_13") (pintype "bidirectional"))
      (node (ref "J3") (pin "1") (pinfunction "1_1") (pintype "passive"))
      (node (ref "R69") (pin "1") (pinfunction "1_1") (pintype "passive"))
    )
    (net (code "137") (name "VCC") (class "Default")
      (node (ref "C1") (pin "1") (pinfunction "1_1") (pintype "passive"))
      (node (ref "C2") (pin "1") (pinfunction "1_1") (pintype "passive"))
      (node (ref "C3") (pin "1") (pinfunction "1_1") (pintype "passive"))
      (node (ref "C4") (pin "1") (pinfunction "1_1") (pintype "passive"))
      (node (ref "IC1") (pin "18") (pinfunction "~{RESET}_18") (pintype "input"))
      (node (ref "IC1") (pin "9") (pinfunction "VDD_9") (pintype "power_in"))
      (node (ref "IC2") (pin "15") (pinfunction "A0_15") (pintype "input"))
      (node (ref "IC2") (pin "18") (pinfunction "~{RESET}_18") (pintype "input"))
      (node (ref "IC2") (pin "9") (pinfunction "VDD_9") (pintype "power_in"))
      (node (ref "IC3") (pin "16") (pinfunction "A1_16") (pintype "input"))
      (node (ref "IC3") (pin "18") (pinfunction "~{RESET}_18") (pintype "input"))
      (node (ref "IC3") (pin "9") (pinfunction "VDD_9") (pintype "power_in"))
      (node (ref "IC4") (pin "15") (pinfunction "A0_15") (pintype "input"))
      (node (ref "IC4") (pin "16") (pinfunction "A1_16") (pintype "input"))
      (node (ref "IC4") (pin "18") (pinfunction "~{RESET}_18") (pintype "input"))
      (node (ref "IC4") (pin "9") (pinfunction "VDD_9") (pintype "power_in"))
      (node (ref "J3") (pin "3") (pinfunction "3_3") (pintype "passive"))
      (node (ref "R39") (pin "2") (pinfunction "2_2") (pintype "passive"))
      (node (ref "SJ1") (pin "2") (pinfunction "2_2") (pintype "passive"))
      (node (ref "SJ2") (pin "2") (pinfunction "2_2") (pintype "passive"))
      (node (ref "SJ3") (pin "2") (pinfunction "2_2") (pintype "passive"))
    )
    (net (code "138") (name "VIN") (class "Default")
      (node (ref "C7") (pin "+") (pinfunction "+_+") (pintype "passive"))
      (node (ref "J1") (pin "A4") (pinfunction "A4_A4") (pintype "bidirectional"))
      (node (ref "J1") (pin "A5") (pinfunction "A5_A5") (pintype "bidirectional"))
      (node (ref "J1") (pin "B4") (pinfunction "B4_B4") (pintype "bidirectional"))
      (node (ref "J1") (pin "B5") (pinfunction "B5_B5") (pintype "bidirectional"))
      (node (ref "J1") (pin "C4") (pinfunction "C4_C4") (pintype "bidirectional"))
      (node (ref "J1") (pin "C5") (pinfunction "C5_C5") (pintype "bidirectional"))
      (node (ref "J1") (pin "D4") (pinfunction "D4_D4") (pintype "bidirectional"))
      (node (ref "J1") (pin "D5") (pinfunction "D5_D5") (pintype "bidirectional"))
      (node (ref "J1") (pin "E4") (pinfunction "E4_E4") (pintype "bidirectional"))
      (node (ref "J1") (pin "E5") (pinfunction "E5_E5") (pintype "bidirectional"))
      (node (ref "J1") (pin "F4") (pinfunction "F4_F4") (pintype "bidirectional"))
      (node (ref "J1") (pin "F5") (pinfunction "F5_F5") (pintype "bidirectional"))
      (node (ref "J1") (pin "G4") (pinfunction "G4_G4") (pintype "bidirectional"))
      (node (ref "J1") (pin "G5") (pinfunction "G5_G5") (pintype "bidirectional"))
      (node (ref "J1") (pin "H4") (pinfunction "H4_H4") (pintype "bidirectional"))
      (node (ref "J1") (pin "H5") (pinfunction "H5_H5") (pintype "bidirectional"))
      (node (ref "J2") (pin "A4") (pinfunction "A4_A4") (pintype "bidirectional"))
      (node (ref "J2") (pin "A5") (pinfunction "A5_A5") (pintype "bidirectional"))
      (node (ref "J2") (pin "B4") (pinfunction "B4_B4") (pintype "bidirectional"))
      (node (ref "J2") (pin "B5") (pinfunction "B5_B5") (pintype "bidirectional"))
      (node (ref "J2") (pin "C4") (pinfunction "C4_C4") (pintype "bidirectional"))
      (node (ref "J2") (pin "C5") (pinfunction "C5_C5") (pintype "bidirectional"))
      (node (ref "J2") (pin "D4") (pinfunction "D4_D4") (pintype "bidirectional"))
      (node (ref "J2") (pin "D5") (pinfunction "D5_D5") (pintype "bidirectional"))
      (node (ref "J2") (pin "E4") (pinfunction "E4_E4") (pintype "bidirectional"))
      (node (ref "J2") (pin "E5") (pinfunction "E5_E5") (pintype "bidirectional"))
      (node (ref "J2") (pin "F4") (pinfunction "F4_F4") (pintype "bidirectional"))
      (node (ref "J2") (pin "F5") (pinfunction "F5_F5") (pintype "bidirectional"))
      (node (ref "J2") (pin "G4") (pinfunction "G4_G4") (pintype "bidirectional"))
      (node (ref "J2") (pin "G5") (pinfunction "G5_G5") (pintype "bidirectional"))
      (node (ref "J2") (pin "H4") (pinfunction "H4_H4") (pintype "bidirectional"))
      (node (ref "J2") (pin "H5") (pinfunction "H5_H5") (pintype "bidirectional"))
      (node (ref "J3") (pin "5") (pinfunction "5_5") (pintype "passive"))
      (node (ref "R40") (pin "2") (pinfunction "2_2") (pintype "passive"))
    )
    (net (code "139") (name "unconnected-(IC1-INTB-Pad19)") (class "Default")
      (node (ref "IC1") (pin "19") (pinfunction "INTB_19") (pintype "output"))
    )
    (net (code "140") (name "unconnected-(IC2-INTB-Pad19)") (class "Default")
      (node (ref "IC2") (pin "19") (pinfunction "INTB_19") (pintype "output"))
    )
    (net (code "141") (name "unconnected-(IC3-INTB-Pad19)") (class "Default")
      (node (ref "IC3") (pin "19") (pinfunction "INTB_19") (pintype "output"))
    )
    (net (code "142") (name "unconnected-(IC4-INTB-Pad19)") (class "Default")
      (node (ref "IC4") (pin "19") (pinfunction "INTB_19") (pintype "output"))
    )
    (net (code "143") (name "~{INT}") (class "Default")
      (node (ref "IC1") (pin "20") (pinfunction "INTA_20") (pintype "output"))
      (node (ref "IC2") (pin "20") (pinfunction "INTA_20") (pintype "output"))
      (node (ref "IC3") (pin "20") (pinfunction "INTA_20") (pintype "output"))
      (node (ref "IC4") (pin "20") (pinfunction "INTA_20") (pintype "output"))
      (node (ref "J3") (pin "6") (pinfunction "6_6") (pintype "passive"))
    )
  )
)
